# 444___1.net
KiCad netlist of a schematic drawn in Altium Designer
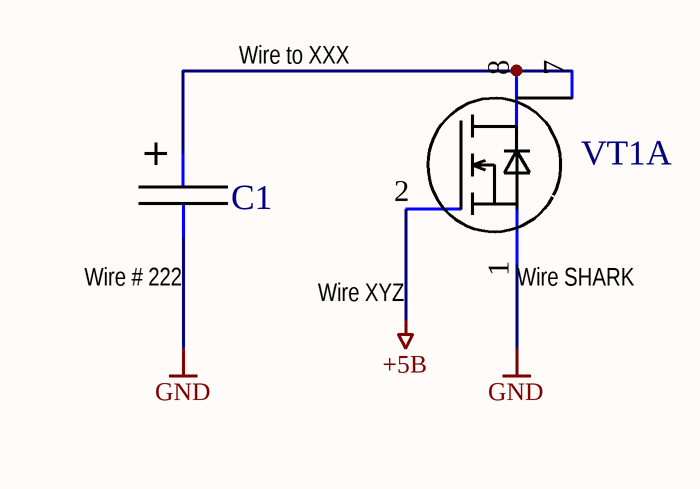
[diagram p0: МИЭТ_444_Лист_1.SchDoc]

(export (version "E")
  (design (tool "Eeschema 10.0.6"))
  (components
    (comp (ref "C1")
      (value "~")
      (footprint "D-Tantal")
      (description "К53-65 Конденсатор танталовый D(7343) 1,5-330 мкФ")
      (fields
        (field (name "MANUFACTURER") "ОАО \"Элеконд\"")
        (field (name "TOLERANCE") "10%")
        (field (name "CREATED_BY") "Желобаев")
      )
      (libsource (lib "Int_Library_for_Lessons_3") (part "K53-65_D_10%"))
    )
    (comp (ref "VT1")
      (value "~")
      (footprint "4320-8-N")
      (description "Транзисторная сборка с n-каналом")
      (fields
        (field (name "MANUFACTURER") "ОАО \"ВЗПП-С\"")
        (field (name "VOLTAGE") "30")
        (field (name "CREATED_BY") "Желобаев")
      )
      (libsource (lib "Int_Library_for_Lessons_3") (part "2П7240АС9"))
    )
  )
  (nets
    (net (code "1") (name "+5В") (class "Default")
      (node (ref "VT1") (pin "2") (pinfunction "G_2") (pintype "passive"))
    )
    (net (code "2") (name "/Wire to XXX") (class "Default")
      (node (ref "C1") (pin "+") (pinfunction "+_+") (pintype "passive"))
      (node (ref "VT1") (pin "7") (pinfunction "D_7") (pintype "passive"))
      (node (ref "VT1") (pin "8") (pinfunction "D_8") (pintype "passive"))
    )
    (net (code "3") (name "GND") (class "Default")
      (node (ref "C1") (pin "-") (pinfunction "-_-") (pintype "passive"))
      (node (ref "VT1") (pin "1") (pinfunction "S_1") (pintype "passive"))
    )
  )
)
